# ESP32-NAT.net
KiCad netlist of a schematic drawn in EasyEDA Pro
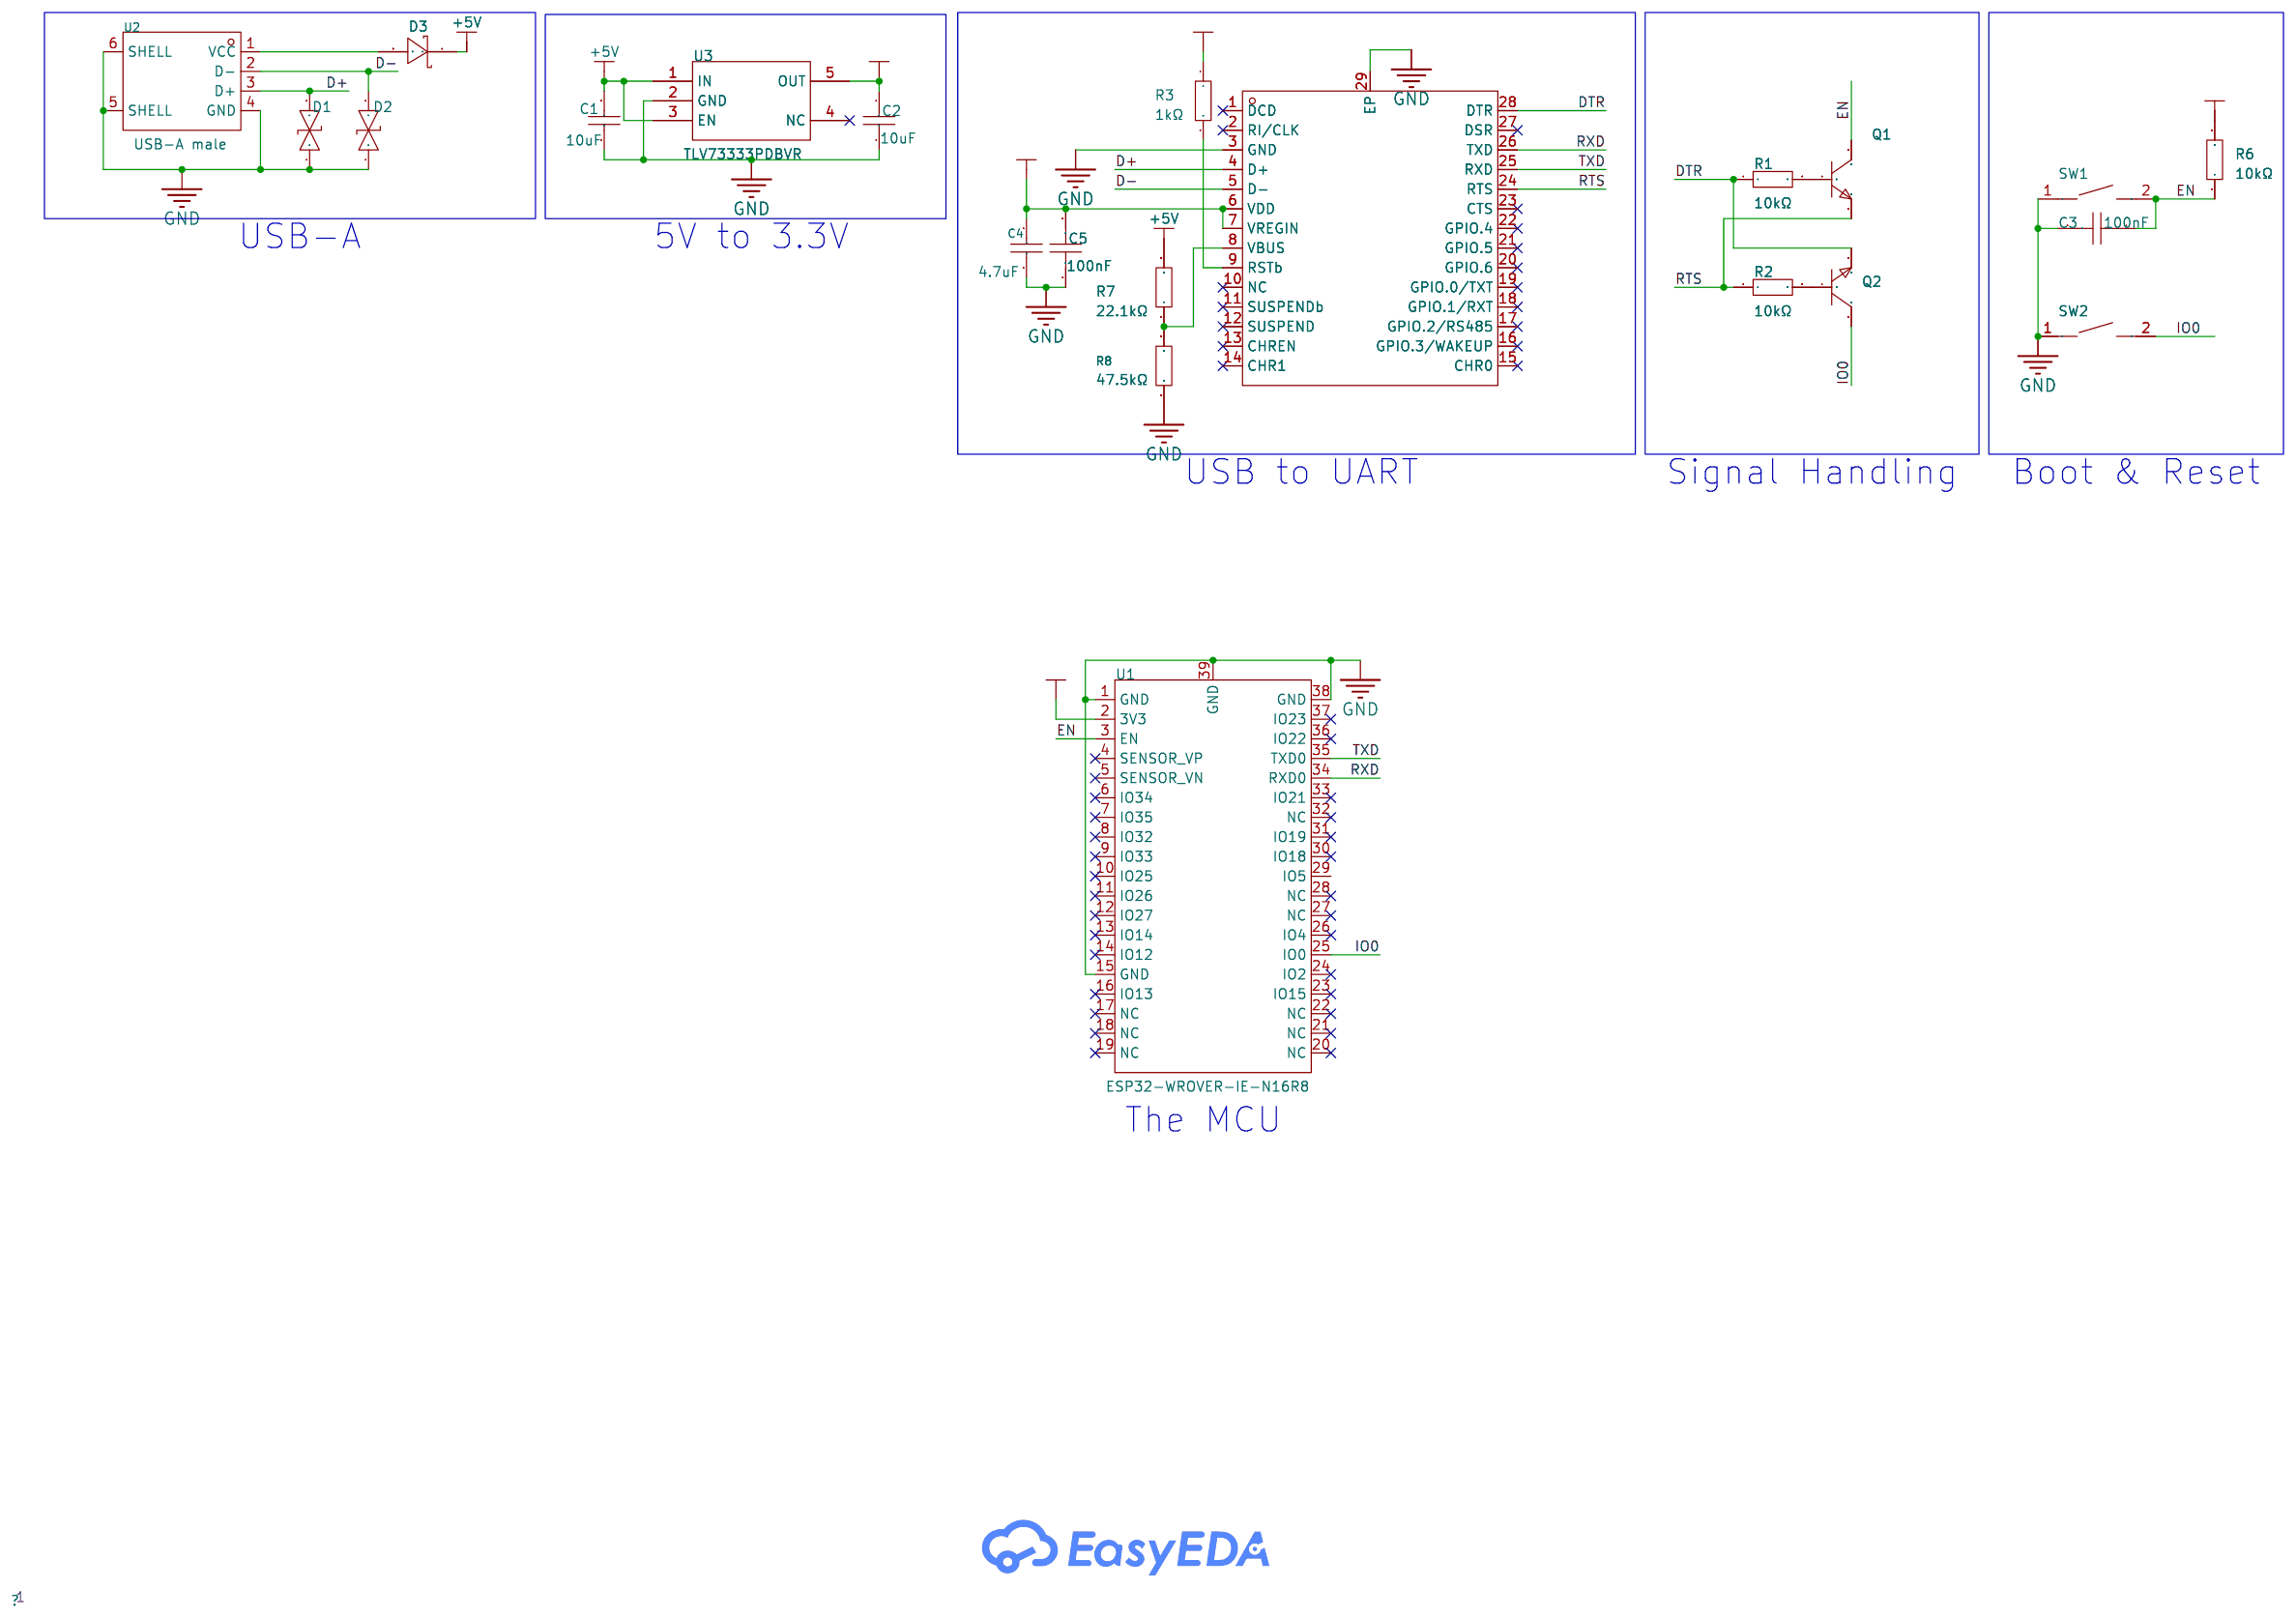
[diagram p0: schematic sheet]

(export (version "E")
  (design (tool "Eeschema 10.0.6"))
  (components
    (comp (ref "C1")
      (value "10uF")
      (footprint "easyedapro:C0402")
      (description "Capacitance:10uF Tolerance:±20% Tolerance:±20% Voltage Rating:6.3V Temperature Coefficient:X5R")
      (fields
        (field (name "Manufacturer Part") "CL05A106MQ5NUNC")
        (field (name "Manufacturer") "SAMSUNG(三星)")
      )
      (libsource (lib "easyedapro") (part "CL05A106MQ5NUNC"))
    )
    (comp (ref "C2")
      (value "10uF")
      (footprint "easyedapro:C0402")
      (description "Capacitance:10uF Tolerance:±20% Tolerance:±20% Voltage Rating:6.3V Temperature Coefficient:X5R")
      (fields
        (field (name "Manufacturer Part") "CL05A106MQ5NUNC")
        (field (name "Manufacturer") "SAMSUNG(三星)")
      )
      (libsource (lib "easyedapro") (part "CL05A106MQ5NUNC"))
    )
    (comp (ref "C3")
      (value "100nF")
      (footprint "easyedapro:C0402")
      (description "Capacitance:100nF Tolerance:±10% Tolerance:±10% Voltage Rating:16V Temperature Coefficient:X7R")
      (fields
        (field (name "Manufacturer Part") "CL05B104KO5NNNC")
        (field (name "Manufacturer") "SAMSUNG(三星)")
      )
      (libsource (lib "easyedapro") (part "CL05B104KO5NNNC"))
    )
    (comp (ref "C4")
      (value "4.7uF")
      (footprint "easyedapro:C0402")
      (description "Capacitance:4.7uF Tolerance:±20% Tolerance:±20% Voltage Rating:10V Temperature Coefficient:X5R")
      (fields
        (field (name "Manufacturer Part") "CL05A475MP5NRNC")
        (field (name "Manufacturer") "SAMSUNG(三星)")
      )
      (libsource (lib "easyedapro") (part "CL05A475MP5NRNC"))
    )
    (comp (ref "C5")
      (value "100nF")
      (footprint "easyedapro:C0402")
      (description "Capacitance:100nF Tolerance:±10% Tolerance:±10% Voltage Rating:16V Temperature Coefficient:X7R")
      (fields
        (field (name "Manufacturer Part") "CL05B104KO5NNNC")
        (field (name "Manufacturer") "SAMSUNG(三星)")
      )
      (libsource (lib "easyedapro") (part "CL05B104KO5NNNC"))
    )
    (comp (ref "D1")
      (value "LESD5D5.0CT1G-ES")
      (footprint "easyedapro:SOD-523_L1.2-W0.8-LS1.6-BI")
      (fields (field (name "Manufacturer") "ElecSuper(静芯微)"))
      (libsource (lib "easyedapro") (part "LESD5D5.0CT1G-ES"))
    )
    (comp (ref "D2")
      (value "LESD5D5.0CT1G-ES")
      (footprint "easyedapro:SOD-523_L1.2-W0.8-LS1.6-BI")
      (fields (field (name "Manufacturer") "ElecSuper(静芯微)"))
      (libsource (lib "easyedapro") (part "LESD5D5.0CT1G-ES"))
    )
    (comp (ref "D3")
      (value "BAT760-7")
      (footprint "easyedapro:SOD-323_L1.8-W1.3-LS2.5-RD")
      (fields (field (name "Manufacturer") "DIODES(美台)"))
      (libsource (lib "easyedapro") (part "BAT760-7"))
    )
    (comp (ref "Q1")
      (value "SS8050-G")
      (footprint "easyedapro:SOT-23-3_L2.9-W1.5-P1.90-LS2.6-BR")
      (fields (field (name "Manufacturer") "Comchip(典琦)"))
      (libsource (lib "easyedapro") (part "SS8050-G_C3199946"))
    )
    (comp (ref "Q2")
      (value "SS8050-G")
      (footprint "easyedapro:SOT-23-3_L2.9-W1.5-P1.90-LS2.6-BR")
      (fields (field (name "Manufacturer") "Comchip(典琦)"))
      (libsource (lib "easyedapro") (part "SS8050-G_C3199946"))
    )
    (comp (ref "R1")
      (value "10kΩ")
      (footprint "easyedapro:R0402")
      (fields
        (field (name "Manufacturer Part") "0402WGF1002TCE")
        (field (name "Manufacturer") "UNI-ROYAL(厚声)")
      )
      (libsource (lib "easyedapro") (part "0402WGF1002TCE"))
    )
    (comp (ref "R2")
      (value "10kΩ")
      (footprint "easyedapro:R0402")
      (fields
        (field (name "Manufacturer Part") "0402WGF1002TCE")
        (field (name "Manufacturer") "UNI-ROYAL(厚声)")
      )
      (libsource (lib "easyedapro") (part "0402WGF1002TCE"))
    )
    (comp (ref "R3")
      (value "1kΩ")
      (fields
        (field (name "Manufacturer Part") "0402WGF1001TCE")
        (field (name "Manufacturer") "UNI-ROYAL(厚声)")
      )
      (libsource (lib "easyedapro") (part "0402WGF1001TCE"))
    )
    (comp (ref "R6")
      (value "10kΩ")
      (footprint "easyedapro:R0402")
      (fields
        (field (name "Manufacturer Part") "0402WGF1002TCE")
        (field (name "Manufacturer") "UNI-ROYAL(厚声)")
      )
      (libsource (lib "easyedapro") (part "0402WGF1002TCE"))
    )
    (comp (ref "R7")
      (value "22.1kΩ")
      (footprint "easyedapro:R0402")
      (fields
        (field (name "Manufacturer Part") "0402WGF2212TCE")
        (field (name "Manufacturer") "UNI-ROYAL(厚声)")
      )
      (libsource (lib "easyedapro") (part "0402WGF2212TCE"))
    )
    (comp (ref "R8")
      (value "47.5kΩ")
      (footprint "easyedapro:R0402")
      (fields
        (field (name "Manufacturer Part") "0402WGF4752TCE")
        (field (name "Manufacturer") "UNI-ROYAL(厚声)")
      )
      (libsource (lib "easyedapro") (part "0402WGF4752TCE"))
    )
    (comp (ref "SW1")
      (value "TS-1088-AR02016")
      (footprint "easyedapro:SW-SMD_L3.9-W3.0-P4.45")
      (fields (field (name "Manufacturer") "XUNPU(讯普)"))
      (libsource (lib "easyedapro") (part "TS-1088-AR02016"))
    )
    (comp (ref "SW2")
      (value "TS-1088-AR02016")
      (footprint "easyedapro:SW-SMD_L3.9-W3.0-P4.45")
      (fields (field (name "Manufacturer") "XUNPU(讯普)"))
      (libsource (lib "easyedapro") (part "TS-1088-AR02016"))
    )
    (comp (ref "U1")
      (value "ESP32-WROVER-IE-N16R8")
      (footprint "easyedapro:WIFI-SMD_ESP32-WROVER-E-N8R2")
      (fields (field (name "Manufacturer") "ESPRESSIF(乐鑫)"))
      (libsource (lib "easyedapro") (part "ESP32-WROVER-IE(16MB)"))
    )
    (comp (ref "U2")
      (value "USB-A male")
      (footprint "easyedapro:USB-SMD_USB-U203-BDS")
      (fields (field (name "Manufacturer") "HANBO(汉博)"))
      (libsource (lib "easyedapro") (part "USB-U203-BDS"))
    )
    (comp (ref "U3")
      (value "TLV73333PDBVR")
      (footprint "easyedapro:SOT-23-5_L3.0-W1.7-P0.95-LS2.8-BR")
      (fields (field (name "Manufacturer") "TI(德州仪器)"))
      (libsource (lib "easyedapro") (part "TLV73333PDBVR"))
    )
    (comp (ref "U4")
      (value "CP2102N-A02-GQFN28R")
      (footprint "easyedapro:QFN-28_L5.0-W5.0-P0.50-TL-EP3.3")
      (fields (field (name "Manufacturer") "SKYWORKS/SILICON LABS(芯科)"))
      (libsource (lib "easyedapro") (part "CP2102N-A02-GQFN28R"))
    )
  )
  (nets
    (net (code "1") (name "+3V3") (class "Default")
      (node (ref "C2") (pin "2") (pinfunction "2_2") (pintype "input"))
      (node (ref "C4") (pin "2") (pinfunction "2_2") (pintype "input"))
      (node (ref "C5") (pin "2") (pinfunction "2_2") (pintype "unspecified"))
      (node (ref "R3") (pin "1") (pinfunction "1_1") (pintype "input"))
      (node (ref "R6") (pin "2") (pinfunction "2_2") (pintype "input"))
      (node (ref "U1") (pin "2") (pinfunction "3V3_2") (pintype "unspecified"))
      (node (ref "U3") (pin "5") (pinfunction "OUT_5") (pintype "unspecified"))
      (node (ref "U4") (pin "6") (pinfunction "VDD_6") (pintype "unspecified"))
      (node (ref "U4") (pin "7") (pinfunction "VREGIN_7") (pintype "unspecified"))
    )
    (net (code "2") (name "+5V") (class "Default")
      (node (ref "C1") (pin "2") (pinfunction "2_2") (pintype "input"))
      (node (ref "D3") (pin "1") (pinfunction "1_1") (pintype "unspecified"))
      (node (ref "R7") (pin "2") (pinfunction "2_2") (pintype "input"))
      (node (ref "U3") (pin "1") (pinfunction "IN_1") (pintype "unspecified"))
      (node (ref "U3") (pin "3") (pinfunction "EN_3") (pintype "unspecified"))
    )
    (net (code "3") (name "/D+") (class "Default")
      (node (ref "D1") (pin "2") (pinfunction "2_2") (pintype "unspecified"))
      (node (ref "U2") (pin "3") (pinfunction "D+_3") (pintype "input"))
      (node (ref "U4") (pin "4") (pinfunction "D+_4") (pintype "unspecified"))
    )
    (net (code "4") (name "/D-") (class "Default")
      (node (ref "D2") (pin "2") (pinfunction "2_2") (pintype "unspecified"))
      (node (ref "U2") (pin "2") (pinfunction "D-_2") (pintype "input"))
      (node (ref "U4") (pin "5") (pinfunction "D-_5") (pintype "unspecified"))
    )
    (net (code "5") (name "/DTR") (class "Default")
      (node (ref "Q2") (pin "2") (pinfunction "E_2") (pintype "input"))
      (node (ref "R1") (pin "1") (pinfunction "1_1") (pintype "input"))
      (node (ref "U4") (pin "28") (pinfunction "DTR_28") (pintype "unspecified"))
    )
    (net (code "6") (name "/EN") (class "Default")
      (node (ref "C3") (pin "1") (pinfunction "1_1") (pintype "unspecified"))
      (node (ref "Q1") (pin "3") (pinfunction "C_3") (pintype "input"))
      (node (ref "R6") (pin "1") (pinfunction "1_1") (pintype "input"))
      (node (ref "SW1") (pin "2") (pinfunction "2_2") (pintype "unspecified"))
      (node (ref "U1") (pin "3") (pinfunction "EN_3") (pintype "unspecified"))
    )
    (net (code "7") (name "/IO0") (class "Default")
      (node (ref "Q2") (pin "3") (pinfunction "C_3") (pintype "input"))
      (node (ref "SW2") (pin "2") (pinfunction "2_2") (pintype "unspecified"))
      (node (ref "U1") (pin "25") (pinfunction "IO0_25") (pintype "unspecified"))
    )
    (net (code "8") (name "/RTS") (class "Default")
      (node (ref "Q1") (pin "2") (pinfunction "E_2") (pintype "input"))
      (node (ref "R2") (pin "1") (pinfunction "1_1") (pintype "input"))
      (node (ref "U4") (pin "24") (pinfunction "RTS_24") (pintype "unspecified"))
    )
    (net (code "9") (name "/RXD") (class "Default")
      (node (ref "U1") (pin "34") (pinfunction "RXD0_34") (pintype "unspecified"))
      (node (ref "U4") (pin "26") (pinfunction "TXD_26") (pintype "unspecified"))
    )
    (net (code "10") (name "/TXD") (class "Default")
      (node (ref "U1") (pin "35") (pinfunction "TXD0_35") (pintype "unspecified"))
      (node (ref "U4") (pin "25") (pinfunction "RXD_25") (pintype "unspecified"))
    )
    (net (code "11") (name "GND") (class "Default")
      (node (ref "C1") (pin "1") (pinfunction "1_1") (pintype "input"))
      (node (ref "C2") (pin "1") (pinfunction "1_1") (pintype "input"))
      (node (ref "C3") (pin "2") (pinfunction "2_2") (pintype "unspecified"))
      (node (ref "C4") (pin "1") (pinfunction "1_1") (pintype "input"))
      (node (ref "C5") (pin "1") (pinfunction "1_1") (pintype "unspecified"))
      (node (ref "D1") (pin "1") (pinfunction "1_1") (pintype "unspecified"))
      (node (ref "D2") (pin "1") (pinfunction "1_1") (pintype "unspecified"))
      (node (ref "R8") (pin "1") (pinfunction "1_1") (pintype "input"))
      (node (ref "SW1") (pin "1") (pinfunction "1_1") (pintype "unspecified"))
      (node (ref "SW2") (pin "1") (pinfunction "1_1") (pintype "unspecified"))
      (node (ref "U1") (pin "1") (pinfunction "GND_1") (pintype "unspecified"))
      (node (ref "U1") (pin "15") (pinfunction "GND_15") (pintype "unspecified"))
      (node (ref "U1") (pin "38") (pinfunction "GND_38") (pintype "unspecified"))
      (node (ref "U1") (pin "39") (pinfunction "GND_39") (pintype "unspecified"))
      (node (ref "U2") (pin "4") (pinfunction "GND_4") (pintype "input"))
      (node (ref "U2") (pin "5") (pinfunction "SHELL_5") (pintype "input"))
      (node (ref "U2") (pin "6") (pinfunction "SHELL_6") (pintype "input"))
      (node (ref "U3") (pin "2") (pinfunction "GND_2") (pintype "unspecified"))
      (node (ref "U4") (pin "29") (pinfunction "EP_29") (pintype "unspecified"))
      (node (ref "U4") (pin "3") (pinfunction "GND_3") (pintype "unspecified"))
    )
    (net (code "12") (name "Net-(Q1-B)") (class "Default")
      (node (ref "Q1") (pin "1") (pinfunction "B_1") (pintype "input"))
      (node (ref "R1") (pin "2") (pinfunction "2_2") (pintype "input"))
    )
    (net (code "13") (name "Net-(Q2-B)") (class "Default")
      (node (ref "Q2") (pin "1") (pinfunction "B_1") (pintype "input"))
      (node (ref "R2") (pin "2") (pinfunction "2_2") (pintype "input"))
    )
    (net (code "14") (name "Net-(U2-VCC)") (class "Default")
      (node (ref "D3") (pin "2") (pinfunction "2_2") (pintype "unspecified"))
      (node (ref "U2") (pin "1") (pinfunction "VCC_1") (pintype "input"))
    )
    (net (code "15") (name "Net-(U4-RSTb)") (class "Default")
      (node (ref "R3") (pin "2") (pinfunction "2_2") (pintype "input"))
      (node (ref "U4") (pin "9") (pinfunction "RSTb_9") (pintype "unspecified"))
    )
    (net (code "16") (name "Net-(U4-VBUS)") (class "Default")
      (node (ref "R7") (pin "1") (pinfunction "1_1") (pintype "input"))
      (node (ref "R8") (pin "2") (pinfunction "2_2") (pintype "input"))
      (node (ref "U4") (pin "8") (pinfunction "VBUS_8") (pintype "unspecified"))
    )
    (net (code "17") (name "unconnected-(U1-IO2-Pad24)") (class "Default")
      (node (ref "U1") (pin "24") (pinfunction "IO2_24") (pintype "unspecified+no_connect"))
    )
    (net (code "18") (name "unconnected-(U1-IO4-Pad26)") (class "Default")
      (node (ref "U1") (pin "26") (pinfunction "IO4_26") (pintype "unspecified+no_connect"))
    )
    (net (code "19") (name "unconnected-(U1-IO5-Pad29)") (class "Default")
      (node (ref "U1") (pin "29") (pinfunction "IO5_29") (pintype "unspecified"))
    )
    (net (code "20") (name "unconnected-(U1-IO12-Pad14)") (class "Default")
      (node (ref "U1") (pin "14") (pinfunction "IO12_14") (pintype "unspecified+no_connect"))
    )
    (net (code "21") (name "unconnected-(U1-IO13-Pad16)") (class "Default")
      (node (ref "U1") (pin "16") (pinfunction "IO13_16") (pintype "unspecified+no_connect"))
    )
    (net (code "22") (name "unconnected-(U1-IO14-Pad13)") (class "Default")
      (node (ref "U1") (pin "13") (pinfunction "IO14_13") (pintype "unspecified+no_connect"))
    )
    (net (code "23") (name "unconnected-(U1-IO15-Pad23)") (class "Default")
      (node (ref "U1") (pin "23") (pinfunction "IO15_23") (pintype "unspecified+no_connect"))
    )
    (net (code "24") (name "unconnected-(U1-IO18-Pad30)") (class "Default")
      (node (ref "U1") (pin "30") (pinfunction "IO18_30") (pintype "unspecified+no_connect"))
    )
    (net (code "25") (name "unconnected-(U1-IO19-Pad31)") (class "Default")
      (node (ref "U1") (pin "31") (pinfunction "IO19_31") (pintype "unspecified+no_connect"))
    )
    (net (code "26") (name "unconnected-(U1-IO21-Pad33)") (class "Default")
      (node (ref "U1") (pin "33") (pinfunction "IO21_33") (pintype "unspecified+no_connect"))
    )
    (net (code "27") (name "unconnected-(U1-IO22-Pad36)") (class "Default")
      (node (ref "U1") (pin "36") (pinfunction "IO22_36") (pintype "unspecified+no_connect"))
    )
    (net (code "28") (name "unconnected-(U1-IO23-Pad37)") (class "Default")
      (node (ref "U1") (pin "37") (pinfunction "IO23_37") (pintype "unspecified+no_connect"))
    )
    (net (code "29") (name "unconnected-(U1-IO25-Pad10)") (class "Default")
      (node (ref "U1") (pin "10") (pinfunction "IO25_10") (pintype "unspecified+no_connect"))
    )
    (net (code "30") (name "unconnected-(U1-IO26-Pad11)") (class "Default")
      (node (ref "U1") (pin "11") (pinfunction "IO26_11") (pintype "unspecified+no_connect"))
    )
    (net (code "31") (name "unconnected-(U1-IO27-Pad12)") (class "Default")
      (node (ref "U1") (pin "12") (pinfunction "IO27_12") (pintype "unspecified+no_connect"))
    )
    (net (code "32") (name "unconnected-(U1-IO32-Pad8)") (class "Default")
      (node (ref "U1") (pin "8") (pinfunction "IO32_8") (pintype "unspecified+no_connect"))
    )
    (net (code "33") (name "unconnected-(U1-IO33-Pad9)") (class "Default")
      (node (ref "U1") (pin "9") (pinfunction "IO33_9") (pintype "unspecified+no_connect"))
    )
    (net (code "34") (name "unconnected-(U1-IO34-Pad6)") (class "Default")
      (node (ref "U1") (pin "6") (pinfunction "IO34_6") (pintype "unspecified+no_connect"))
    )
    (net (code "35") (name "unconnected-(U1-IO35-Pad7)") (class "Default")
      (node (ref "U1") (pin "7") (pinfunction "IO35_7") (pintype "unspecified+no_connect"))
    )
    (net (code "36") (name "unconnected-(U1-NC-Pad17)") (class "Default")
      (node (ref "U1") (pin "17") (pinfunction "NC_17") (pintype "unspecified+no_connect"))
    )
    (net (code "37") (name "unconnected-(U1-NC-Pad18)") (class "Default")
      (node (ref "U1") (pin "18") (pinfunction "NC_18") (pintype "unspecified+no_connect"))
    )
    (net (code "38") (name "unconnected-(U1-NC-Pad19)") (class "Default")
      (node (ref "U1") (pin "19") (pinfunction "NC_19") (pintype "unspecified+no_connect"))
    )
    (net (code "39") (name "unconnected-(U1-NC-Pad20)") (class "Default")
      (node (ref "U1") (pin "20") (pinfunction "NC_20") (pintype "unspecified+no_connect"))
    )
    (net (code "40") (name "unconnected-(U1-NC-Pad21)") (class "Default")
      (node (ref "U1") (pin "21") (pinfunction "NC_21") (pintype "unspecified+no_connect"))
    )
    (net (code "41") (name "unconnected-(U1-NC-Pad22)") (class "Default")
      (node (ref "U1") (pin "22") (pinfunction "NC_22") (pintype "unspecified+no_connect"))
    )
    (net (code "42") (name "unconnected-(U1-NC-Pad27)") (class "Default")
      (node (ref "U1") (pin "27") (pinfunction "NC_27") (pintype "unspecified+no_connect"))
    )
    (net (code "43") (name "unconnected-(U1-NC-Pad28)") (class "Default")
      (node (ref "U1") (pin "28") (pinfunction "NC_28") (pintype "unspecified+no_connect"))
    )
    (net (code "44") (name "unconnected-(U1-NC-Pad32)") (class "Default")
      (node (ref "U1") (pin "32") (pinfunction "NC_32") (pintype "unspecified+no_connect"))
    )
    (net (code "45") (name "unconnected-(U1-SENSOR_VN-Pad5)") (class "Default")
      (node (ref "U1") (pin "5") (pinfunction "SENSOR_VN_5") (pintype "unspecified+no_connect"))
    )
    (net (code "46") (name "unconnected-(U1-SENSOR_VP-Pad4)") (class "Default")
      (node (ref "U1") (pin "4") (pinfunction "SENSOR_VP_4") (pintype "unspecified+no_connect"))
    )
    (net (code "47") (name "unconnected-(U3-NC-Pad4)") (class "Default")
      (node (ref "U3") (pin "4") (pinfunction "NC_4") (pintype "unspecified+no_connect"))
    )
    (net (code "48") (name "unconnected-(U4-CHR0-Pad15)") (class "Default")
      (node (ref "U4") (pin "15") (pinfunction "CHR0_15") (pintype "unspecified+no_connect"))
    )
    (net (code "49") (name "unconnected-(U4-CHR1-Pad14)") (class "Default")
      (node (ref "U4") (pin "14") (pinfunction "CHR1_14") (pintype "unspecified+no_connect"))
    )
    (net (code "50") (name "unconnected-(U4-CHREN-Pad13)") (class "Default")
      (node (ref "U4") (pin "13") (pinfunction "CHREN_13") (pintype "unspecified+no_connect"))
    )
    (net (code "51") (name "unconnected-(U4-CTS-Pad23)") (class "Default")
      (node (ref "U4") (pin "23") (pinfunction "CTS_23") (pintype "unspecified+no_connect"))
    )
    (net (code "52") (name "unconnected-(U4-DCD-Pad1)") (class "Default")
      (node (ref "U4") (pin "1") (pinfunction "DCD_1") (pintype "unspecified+no_connect"))
    )
    (net (code "53") (name "unconnected-(U4-DSR-Pad27)") (class "Default")
      (node (ref "U4") (pin "27") (pinfunction "DSR_27") (pintype "unspecified+no_connect"))
    )
    (net (code "54") (name "unconnected-(U4-GPIO.0{slash}TXT-Pad19)") (class "Default")
      (node (ref "U4") (pin "19") (pinfunction "GPIO.0/TXT_19") (pintype "unspecified+no_connect"))
    )
    (net (code "55") (name "unconnected-(U4-GPIO.1{slash}RXT-Pad18)") (class "Default")
      (node (ref "U4") (pin "18") (pinfunction "GPIO.1/RXT_18") (pintype "unspecified+no_connect"))
    )
    (net (code "56") (name "unconnected-(U4-GPIO.2{slash}RS485-Pad17)") (class "Default")
      (node (ref "U4") (pin "17") (pinfunction "GPIO.2/RS485_17") (pintype "unspecified+no_connect"))
    )
    (net (code "57") (name "unconnected-(U4-GPIO.3{slash}WAKEUP-Pad16)") (class "Default")
      (node (ref "U4") (pin "16") (pinfunction "GPIO.3/WAKEUP_16") (pintype "unspecified+no_connect"))
    )
    (net (code "58") (name "unconnected-(U4-GPIO.4-Pad22)") (class "Default")
      (node (ref "U4") (pin "22") (pinfunction "GPIO.4_22") (pintype "unspecified+no_connect"))
    )
    (net (code "59") (name "unconnected-(U4-GPIO.5-Pad21)") (class "Default")
      (node (ref "U4") (pin "21") (pinfunction "GPIO.5_21") (pintype "unspecified+no_connect"))
    )
    (net (code "60") (name "unconnected-(U4-GPIO.6-Pad20)") (class "Default")
      (node (ref "U4") (pin "20") (pinfunction "GPIO.6_20") (pintype "unspecified+no_connect"))
    )
    (net (code "61") (name "unconnected-(U4-NC-Pad10)") (class "Default")
      (node (ref "U4") (pin "10") (pinfunction "NC_10") (pintype "unspecified+no_connect"))
    )
    (net (code "62") (name "unconnected-(U4-RI{slash}CLK-Pad2)") (class "Default")
      (node (ref "U4") (pin "2") (pinfunction "RI/CLK_2") (pintype "unspecified+no_connect"))
    )
    (net (code "63") (name "unconnected-(U4-SUSPEND-Pad12)") (class "Default")
      (node (ref "U4") (pin "12") (pinfunction "SUSPEND_12") (pintype "unspecified+no_connect"))
    )
    (net (code "64") (name "unconnected-(U4-SUSPENDb-Pad11)") (class "Default")
      (node (ref "U4") (pin "11") (pinfunction "SUSPENDb_11") (pintype "unspecified+no_connect"))
    )
  )
)
